# HC01.net
KiCad netlist of a schematic drawn in Altium Designer
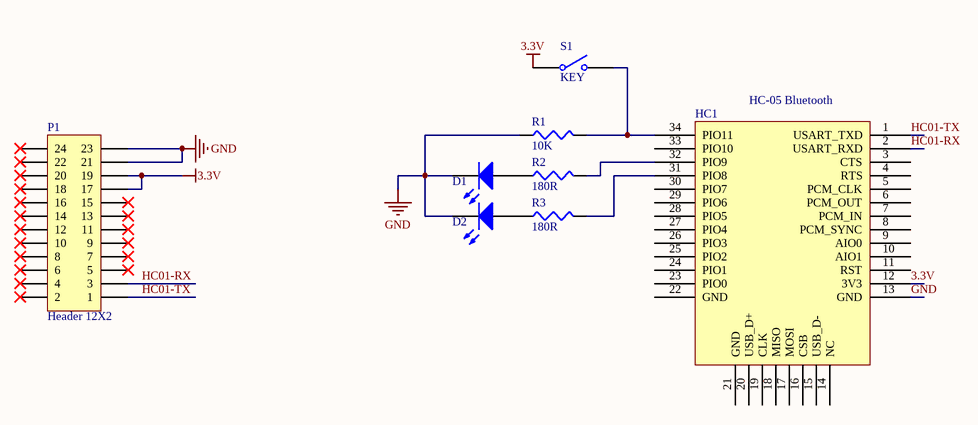
[diagram p0: HC01.SchDoc]

(export (version "E")
  (design (tool "Eeschema 10.0.6"))
  (components
    (comp (ref "D1")
      (value "LED2")
      (footprint "3.2X1.6X1.1")
      (description "Typical RED, GREEN, YELLOW, AMBER GaAs LED")
      (fields (field (name "PUBLISHER") "Altium Limited"))
      (libsource (lib "Miscellaneous Devices") (part "LED2"))
    )
    (comp (ref "D2")
      (value "LED2")
      (footprint "3.2X1.6X1.1")
      (description "Typical RED, GREEN, YELLOW, AMBER GaAs LED")
      (fields (field (name "PUBLISHER") "Altium Limited"))
      (libsource (lib "Miscellaneous Devices") (part "LED2"))
    )
    (comp (ref "HC1")
      (value "HC-05 Bluetooth")
      (footprint "HC-05")
      (libsource (lib "HC-05 Bluetooth") (part "HC-05 Bluetooth"))
    )
    (comp (ref "P1")
      (value "Header 12X2")
      (footprint "HDR2X12")
      (description "Header, 12-Pin, Dual row")
      (fields (field (name "PUBLISHER") "Altium Limited"))
      (libsource (lib "Miscellaneous Connectors") (part "Header 12X2"))
    )
    (comp (ref "R1")
      (value "10K")
      (footprint "1206")
      (description "Resistor")
      (fields (field (name "PUBLISHER") "Altium Limited"))
      (libsource (lib "Miscellaneous Devices") (part "Res3"))
    )
    (comp (ref "R2")
      (value "180R")
      (footprint "1206")
      (description "Resistor")
      (fields (field (name "PUBLISHER") "Altium Limited"))
      (libsource (lib "Miscellaneous Devices") (part "Res3"))
    )
    (comp (ref "R3")
      (value "180R")
      (footprint "1206")
      (description "Resistor")
      (fields (field (name "PUBLISHER") "Altium Limited"))
      (libsource (lib "Miscellaneous Devices") (part "Res3"))
    )
    (comp (ref "S1")
      (value "KEY")
      (footprint "SW-SMD")
      (description "Single-Pole, Single-Throw Switch")
      (fields (field (name "PUBLISHER") "Altium Limited"))
      (libsource (lib "Miscellaneous Devices") (part "SW-SPST"))
    )
  )
  (nets
    (net (code "1") (name "/HC01-RX") (class "Default")
      (node (ref "HC1") (pin "2") (pinfunction "USART_RXD_2") (pintype "passive"))
      (node (ref "P1") (pin "3") (pinfunction "3_3") (pintype "passive"))
    )
    (net (code "2") (name "/HC01-TX") (class "Default")
      (node (ref "HC1") (pin "1") (pinfunction "USART_TXD_1") (pintype "passive"))
      (node (ref "P1") (pin "1") (pinfunction "1_1") (pintype "passive"))
    )
    (net (code "3") (name "3.3V") (class "Default")
      (node (ref "HC1") (pin "12") (pinfunction "3V3_12") (pintype "passive"))
      (node (ref "P1") (pin "17") (pinfunction "17_17") (pintype "passive"))
      (node (ref "P1") (pin "19") (pinfunction "19_19") (pintype "passive"))
      (node (ref "S1") (pin "1") (pinfunction "COMMON_1") (pintype "passive"))
    )
    (net (code "4") (name "GND") (class "Default")
      (node (ref "D1") (pin "2") (pinfunction "K_2") (pintype "passive"))
      (node (ref "D2") (pin "2") (pinfunction "K_2") (pintype "passive"))
      (node (ref "HC1") (pin "13") (pinfunction "GND_13") (pintype "passive"))
      (node (ref "P1") (pin "21") (pinfunction "21_21") (pintype "passive"))
      (node (ref "P1") (pin "23") (pinfunction "23_23") (pintype "passive"))
      (node (ref "R1") (pin "1") (pinfunction "1_1") (pintype "passive"))
    )
    (net (code "5") (name "Net-(D1-A)") (class "Default")
      (node (ref "D1") (pin "1") (pinfunction "A_1") (pintype "passive"))
      (node (ref "R2") (pin "1") (pinfunction "1_1") (pintype "passive"))
    )
    (net (code "6") (name "Net-(D2-A)") (class "Default")
      (node (ref "D2") (pin "1") (pinfunction "A_1") (pintype "passive"))
      (node (ref "R3") (pin "1") (pinfunction "1_1") (pintype "passive"))
    )
    (net (code "7") (name "Net-(HC1-PIO8)") (class "Default")
      (node (ref "HC1") (pin "31") (pinfunction "PIO8_31") (pintype "passive"))
      (node (ref "R3") (pin "2") (pinfunction "2_2") (pintype "passive"))
    )
    (net (code "8") (name "Net-(HC1-PIO9)") (class "Default")
      (node (ref "HC1") (pin "32") (pinfunction "PIO9_32") (pintype "passive"))
      (node (ref "R2") (pin "2") (pinfunction "2_2") (pintype "passive"))
    )
    (net (code "9") (name "Net-(HC1-PIO11)") (class "Default")
      (node (ref "HC1") (pin "34") (pinfunction "PIO11_34") (pintype "passive"))
      (node (ref "R1") (pin "2") (pinfunction "2_2") (pintype "passive"))
      (node (ref "S1") (pin "2") (pinfunction "NO_2") (pintype "passive"))
    )
    (net (code "10") (name "unconnected-(HC1-AIO0-Pad9)") (class "Default")
      (node (ref "HC1") (pin "9") (pinfunction "AIO0_9") (pintype "passive"))
    )
    (net (code "11") (name "unconnected-(HC1-AIO1-Pad10)") (class "Default")
      (node (ref "HC1") (pin "10") (pinfunction "AIO1_10") (pintype "passive"))
    )
    (net (code "12") (name "unconnected-(HC1-CLK-Pad19)") (class "Default")
      (node (ref "HC1") (pin "19") (pinfunction "CLK_19") (pintype "passive"))
    )
    (net (code "13") (name "unconnected-(HC1-CSB-Pad16)") (class "Default")
      (node (ref "HC1") (pin "16") (pinfunction "CSB_16") (pintype "passive"))
    )
    (net (code "14") (name "unconnected-(HC1-CTS-Pad3)") (class "Default")
      (node (ref "HC1") (pin "3") (pinfunction "CTS_3") (pintype "passive"))
    )
    (net (code "15") (name "unconnected-(HC1-GND-Pad21)") (class "Default")
      (node (ref "HC1") (pin "21") (pinfunction "GND_21") (pintype "passive"))
    )
    (net (code "16") (name "unconnected-(HC1-GND-Pad22)") (class "Default")
      (node (ref "HC1") (pin "22") (pinfunction "GND_22") (pintype "passive"))
    )
    (net (code "17") (name "unconnected-(HC1-MISO-Pad18)") (class "Default")
      (node (ref "HC1") (pin "18") (pinfunction "MISO_18") (pintype "passive"))
    )
    (net (code "18") (name "unconnected-(HC1-MOSI-Pad17)") (class "Default")
      (node (ref "HC1") (pin "17") (pinfunction "MOSI_17") (pintype "passive"))
    )
    (net (code "19") (name "unconnected-(HC1-NC-Pad14)") (class "Default")
      (node (ref "HC1") (pin "14") (pinfunction "NC_14") (pintype "passive"))
    )
    (net (code "20") (name "unconnected-(HC1-PCM_CLK-Pad5)") (class "Default")
      (node (ref "HC1") (pin "5") (pinfunction "PCM_CLK_5") (pintype "passive"))
    )
    (net (code "21") (name "unconnected-(HC1-PCM_IN-Pad7)") (class "Default")
      (node (ref "HC1") (pin "7") (pinfunction "PCM_IN_7") (pintype "passive"))
    )
    (net (code "22") (name "unconnected-(HC1-PCM_OUT-Pad6)") (class "Default")
      (node (ref "HC1") (pin "6") (pinfunction "PCM_OUT_6") (pintype "passive"))
    )
    (net (code "23") (name "unconnected-(HC1-PCM_SYNC-Pad8)") (class "Default")
      (node (ref "HC1") (pin "8") (pinfunction "PCM_SYNC_8") (pintype "passive"))
    )
    (net (code "24") (name "unconnected-(HC1-PIO0-Pad23)") (class "Default")
      (node (ref "HC1") (pin "23") (pinfunction "PIO0_23") (pintype "passive"))
    )
    (net (code "25") (name "unconnected-(HC1-PIO1-Pad24)") (class "Default")
      (node (ref "HC1") (pin "24") (pinfunction "PIO1_24") (pintype "passive"))
    )
    (net (code "26") (name "unconnected-(HC1-PIO2-Pad25)") (class "Default")
      (node (ref "HC1") (pin "25") (pinfunction "PIO2_25") (pintype "passive"))
    )
    (net (code "27") (name "unconnected-(HC1-PIO3-Pad26)") (class "Default")
      (node (ref "HC1") (pin "26") (pinfunction "PIO3_26") (pintype "passive"))
    )
    (net (code "28") (name "unconnected-(HC1-PIO4-Pad27)") (class "Default")
      (node (ref "HC1") (pin "27") (pinfunction "PIO4_27") (pintype "passive"))
    )
    (net (code "29") (name "unconnected-(HC1-PIO5-Pad28)") (class "Default")
      (node (ref "HC1") (pin "28") (pinfunction "PIO5_28") (pintype "passive"))
    )
    (net (code "30") (name "unconnected-(HC1-PIO6-Pad29)") (class "Default")
      (node (ref "HC1") (pin "29") (pinfunction "PIO6_29") (pintype "passive"))
    )
    (net (code "31") (name "unconnected-(HC1-PIO7-Pad30)") (class "Default")
      (node (ref "HC1") (pin "30") (pinfunction "PIO7_30") (pintype "passive"))
    )
    (net (code "32") (name "unconnected-(HC1-PIO10-Pad33)") (class "Default")
      (node (ref "HC1") (pin "33") (pinfunction "PIO10_33") (pintype "passive"))
    )
    (net (code "33") (name "unconnected-(HC1-RST-Pad11)") (class "Default")
      (node (ref "HC1") (pin "11") (pinfunction "RST_11") (pintype "passive"))
    )
    (net (code "34") (name "unconnected-(HC1-RTS-Pad4)") (class "Default")
      (node (ref "HC1") (pin "4") (pinfunction "RTS_4") (pintype "passive"))
    )
    (net (code "35") (name "unconnected-(HC1-USB_D+-Pad20)") (class "Default")
      (node (ref "HC1") (pin "20") (pinfunction "USB_D+_20") (pintype "passive"))
    )
    (net (code "36") (name "unconnected-(HC1-USB_D--Pad15)") (class "Default")
      (node (ref "HC1") (pin "15") (pinfunction "USB_D-_15") (pintype "passive"))
    )
    (net (code "37") (name "unconnected-(P1-Pad2)") (class "Default")
      (node (ref "P1") (pin "2") (pinfunction "2_2") (pintype "passive+no_connect"))
    )
    (net (code "38") (name "unconnected-(P1-Pad4)") (class "Default")
      (node (ref "P1") (pin "4") (pinfunction "4_4") (pintype "passive+no_connect"))
    )
    (net (code "39") (name "unconnected-(P1-Pad5)") (class "Default")
      (node (ref "P1") (pin "5") (pinfunction "5_5") (pintype "passive+no_connect"))
    )
    (net (code "40") (name "unconnected-(P1-Pad6)") (class "Default")
      (node (ref "P1") (pin "6") (pinfunction "6_6") (pintype "passive+no_connect"))
    )
    (net (code "41") (name "unconnected-(P1-Pad7)") (class "Default")
      (node (ref "P1") (pin "7") (pinfunction "7_7") (pintype "passive+no_connect"))
    )
    (net (code "42") (name "unconnected-(P1-Pad8)") (class "Default")
      (node (ref "P1") (pin "8") (pinfunction "8_8") (pintype "passive+no_connect"))
    )
    (net (code "43") (name "unconnected-(P1-Pad9)") (class "Default")
      (node (ref "P1") (pin "9") (pinfunction "9_9") (pintype "passive+no_connect"))
    )
    (net (code "44") (name "unconnected-(P1-Pad10)") (class "Default")
      (node (ref "P1") (pin "10") (pinfunction "10_10") (pintype "passive+no_connect"))
    )
    (net (code "45") (name "unconnected-(P1-Pad11)") (class "Default")
      (node (ref "P1") (pin "11") (pinfunction "11_11") (pintype "passive+no_connect"))
    )
    (net (code "46") (name "unconnected-(P1-Pad12)") (class "Default")
      (node (ref "P1") (pin "12") (pinfunction "12_12") (pintype "passive+no_connect"))
    )
    (net (code "47") (name "unconnected-(P1-Pad13)") (class "Default")
      (node (ref "P1") (pin "13") (pinfunction "13_13") (pintype "passive+no_connect"))
    )
    (net (code "48") (name "unconnected-(P1-Pad14)") (class "Default")
      (node (ref "P1") (pin "14") (pinfunction "14_14") (pintype "passive+no_connect"))
    )
    (net (code "49") (name "unconnected-(P1-Pad15)") (class "Default")
      (node (ref "P1") (pin "15") (pinfunction "15_15") (pintype "passive+no_connect"))
    )
    (net (code "50") (name "unconnected-(P1-Pad16)") (class "Default")
      (node (ref "P1") (pin "16") (pinfunction "16_16") (pintype "passive+no_connect"))
    )
    (net (code "51") (name "unconnected-(P1-Pad18)") (class "Default")
      (node (ref "P1") (pin "18") (pinfunction "18_18") (pintype "passive+no_connect"))
    )
    (net (code "52") (name "unconnected-(P1-Pad20)") (class "Default")
      (node (ref "P1") (pin "20") (pinfunction "20_20") (pintype "passive+no_connect"))
    )
    (net (code "53") (name "unconnected-(P1-Pad22)") (class "Default")
      (node (ref "P1") (pin "22") (pinfunction "22_22") (pintype "passive+no_connect"))
    )
    (net (code "54") (name "unconnected-(P1-Pad24)") (class "Default")
      (node (ref "P1") (pin "24") (pinfunction "24_24") (pintype "passive+no_connect"))
    )
  )
)
